# ESP-Power.net
KiCad netlist of a schematic drawn in Altium Designer
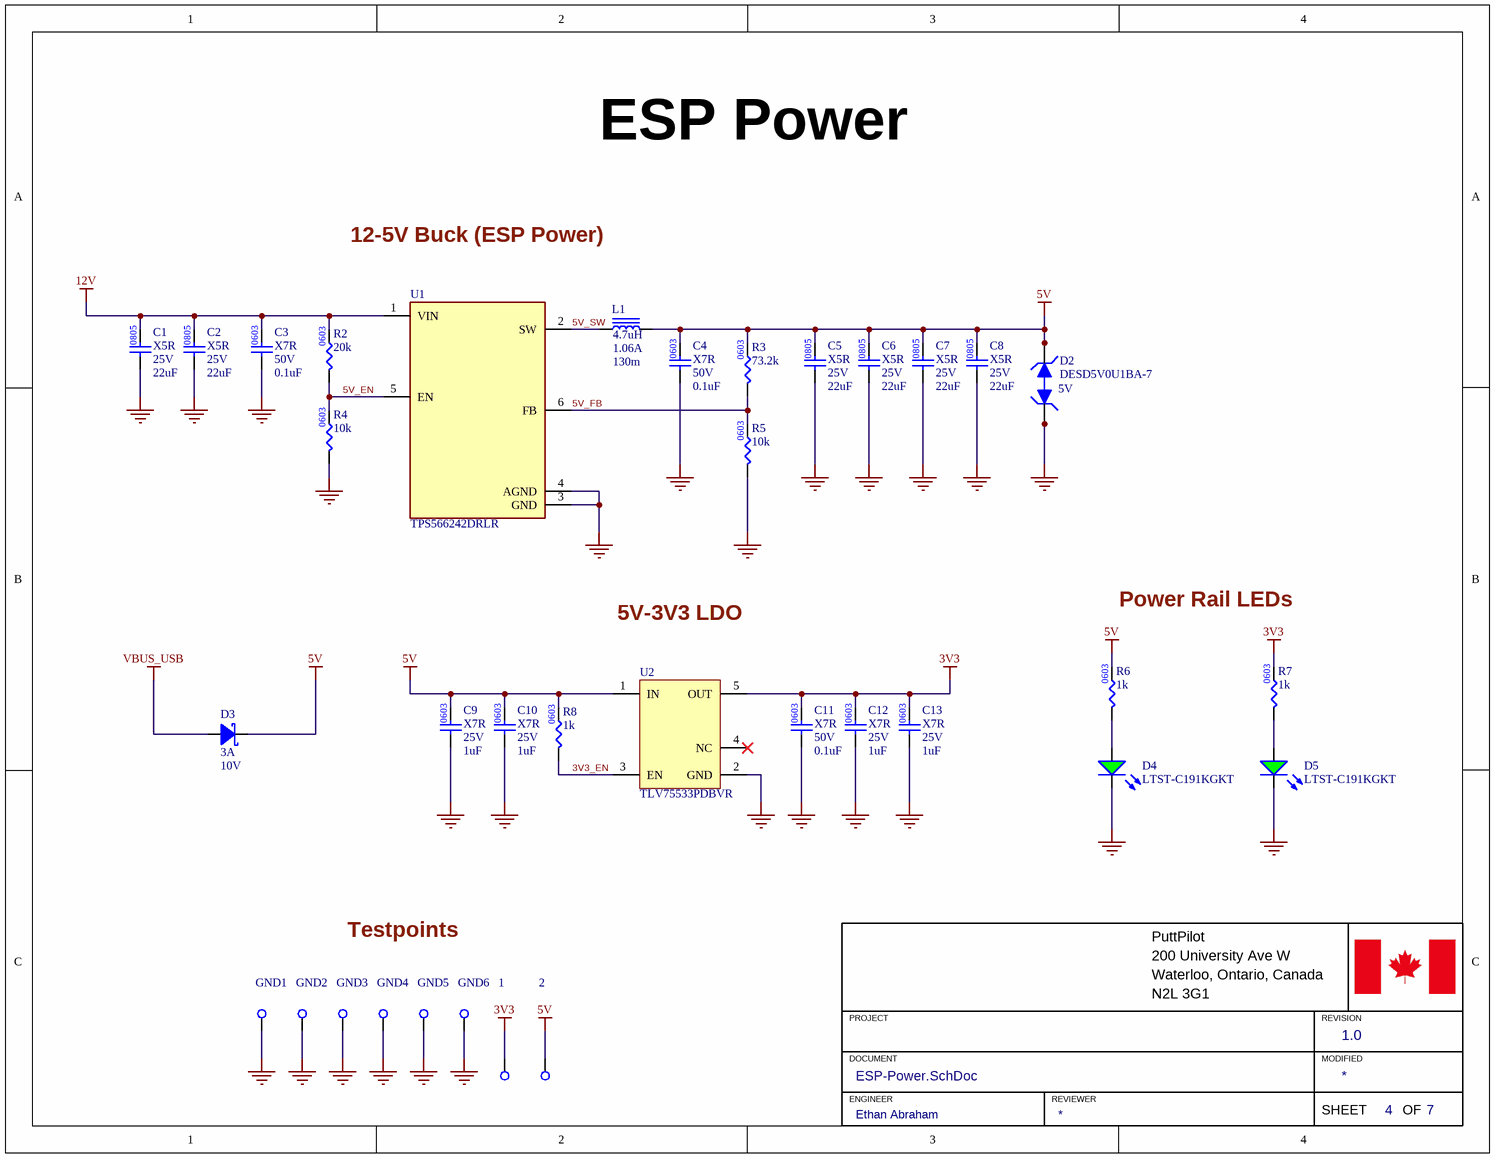
[diagram p0: ESP-Power.SchDoc]

(export (version "E")
  (design (tool "Eeschema 10.0.6"))
  (components
    (comp (ref "1")
      (value "RCWCTE")
      (footprint "RCWCTE")
      (description "SMT Test Point")
      (fields (field (name "MANUFACTURER") "KOA Speer"))
      (libsource (lib "PuttPilot") (part "RCWCTE"))
    )
    (comp (ref "2")
      (value "RCWCTE")
      (footprint "RCWCTE")
      (description "SMT Test Point")
      (fields (field (name "MANUFACTURER") "KOA Speer"))
      (libsource (lib "PuttPilot") (part "RCWCTE"))
    )
    (comp (ref "C1")
      (value "GRM21BR61E226ME44K")
      (footprint ".CAP_0805")
      (description "CAP CER 22uF 25V X5R 0805")
      (fields
        (field (name "MANUFACTURER") "Murata")
        (field (name "TEMPERATURE CHARACTERISTICS CODE") "X5R")
        (field (name "RATED DC VOLTAGE (URDC)") "25V")
        (field (name "CAPACITANCE") "22uF")
      )
      (libsource (lib "PuttPilot") (part "GRM21BR61E226ME44K"))
    )
    (comp (ref "C2")
      (value "GRM21BR61E226ME44K")
      (footprint ".CAP_0805")
      (description "CAP CER 22uF 25V X5R 0805")
      (fields
        (field (name "MANUFACTURER") "Murata")
        (field (name "TEMPERATURE CHARACTERISTICS CODE") "X5R")
        (field (name "RATED DC VOLTAGE (URDC)") "25V")
        (field (name "CAPACITANCE") "22uF")
      )
      (libsource (lib "PuttPilot") (part "GRM21BR61E226ME44K"))
    )
    (comp (ref "C3")
      (value "GCJ188R71H104KA12D")
      (footprint ".CAP_0603")
      (description "CAP CER 0.1uF 50V X7R 0603")
      (fields
        (field (name "MANUFACTURER") "Murata")
        (field (name "TEMPERATURE CHARACTERISTICS CODE") "X7R")
        (field (name "RATED DC VOLTAGE (URDC)") "50V")
        (field (name "CAPACITANCE") "0.1uF")
      )
      (libsource (lib "PuttPilot") (part "GCJ188R71H104KA12D"))
    )
    (comp (ref "C4")
      (value "GCJ188R71H104KA12D")
      (footprint ".CAP_0603")
      (description "CAP CER 0.1uF 50V X7R 0603")
      (fields
        (field (name "MANUFACTURER") "Murata")
        (field (name "TEMPERATURE CHARACTERISTICS CODE") "X7R")
        (field (name "RATED DC VOLTAGE (URDC)") "50V")
        (field (name "CAPACITANCE") "0.1uF")
      )
      (libsource (lib "PuttPilot") (part "GCJ188R71H104KA12D"))
    )
    (comp (ref "C5")
      (value "GRM21BR61E226ME44K")
      (footprint ".CAP_0805")
      (description "CAP CER 22uF 25V X5R 0805")
      (fields
        (field (name "MANUFACTURER") "Murata")
        (field (name "TEMPERATURE CHARACTERISTICS CODE") "X5R")
        (field (name "RATED DC VOLTAGE (URDC)") "25V")
        (field (name "CAPACITANCE") "22uF")
      )
      (libsource (lib "PuttPilot") (part "GRM21BR61E226ME44K"))
    )
    (comp (ref "C6")
      (value "GRM21BR61E226ME44K")
      (footprint ".CAP_0805")
      (description "CAP CER 22uF 25V X5R 0805")
      (fields
        (field (name "MANUFACTURER") "Murata")
        (field (name "TEMPERATURE CHARACTERISTICS CODE") "X5R")
        (field (name "RATED DC VOLTAGE (URDC)") "25V")
        (field (name "CAPACITANCE") "22uF")
      )
      (libsource (lib "PuttPilot") (part "GRM21BR61E226ME44K"))
    )
    (comp (ref "C7")
      (value "GRM21BR61E226ME44K")
      (footprint ".CAP_0805")
      (description "CAP CER 22uF 25V X5R 0805")
      (fields
        (field (name "MANUFACTURER") "Murata")
        (field (name "TEMPERATURE CHARACTERISTICS CODE") "X5R")
        (field (name "RATED DC VOLTAGE (URDC)") "25V")
        (field (name "CAPACITANCE") "22uF")
      )
      (libsource (lib "PuttPilot") (part "GRM21BR61E226ME44K"))
    )
    (comp (ref "C8")
      (value "GRM21BR61E226ME44K")
      (footprint ".CAP_0805")
      (description "CAP CER 22uF 25V X5R 0805")
      (fields
        (field (name "MANUFACTURER") "Murata")
        (field (name "TEMPERATURE CHARACTERISTICS CODE") "X5R")
        (field (name "RATED DC VOLTAGE (URDC)") "25V")
        (field (name "CAPACITANCE") "22uF")
      )
      (libsource (lib "PuttPilot") (part "GRM21BR61E226ME44K"))
    )
    (comp (ref "C9")
      (value "GRT188R71E105KE13D")
      (footprint ".CAP_0603")
      (description "CAP CER 1uF 25V X7R 0603")
      (fields
        (field (name "MANUFACTURER") "Murata")
        (field (name "TEMPERATURE CHARACTERISTICS CODE") "X7R")
        (field (name "RATED DC VOLTAGE (URDC)") "25V")
        (field (name "CAPACITANCE") "1uF")
      )
      (libsource (lib "PuttPilot") (part "GRT188R71E105KE13D"))
    )
    (comp (ref "C10")
      (value "GRT188R71E105KE13D")
      (footprint ".CAP_0603")
      (description "CAP CER 1uF 25V X7R 0603")
      (fields
        (field (name "MANUFACTURER") "Murata")
        (field (name "TEMPERATURE CHARACTERISTICS CODE") "X7R")
        (field (name "RATED DC VOLTAGE (URDC)") "25V")
        (field (name "CAPACITANCE") "1uF")
      )
      (libsource (lib "PuttPilot") (part "GRT188R71E105KE13D"))
    )
    (comp (ref "C11")
      (value "GCJ188R71H104KA12D")
      (footprint ".CAP_0603")
      (description "CAP CER 0.1uF 50V X7R 0603")
      (fields
        (field (name "MANUFACTURER") "Murata")
        (field (name "TEMPERATURE CHARACTERISTICS CODE") "X7R")
        (field (name "RATED DC VOLTAGE (URDC)") "50V")
        (field (name "CAPACITANCE") "0.1uF")
      )
      (libsource (lib "PuttPilot") (part "GCJ188R71H104KA12D"))
    )
    (comp (ref "C12")
      (value "GRT188R71E105KE13D")
      (footprint ".CAP_0603")
      (description "CAP CER 1uF 25V X7R 0603")
      (fields
        (field (name "MANUFACTURER") "Murata")
        (field (name "TEMPERATURE CHARACTERISTICS CODE") "X7R")
        (field (name "RATED DC VOLTAGE (URDC)") "25V")
        (field (name "CAPACITANCE") "1uF")
      )
      (libsource (lib "PuttPilot") (part "GRT188R71E105KE13D"))
    )
    (comp (ref "C13")
      (value "GRT188R71E105KE13D")
      (footprint ".CAP_0603")
      (description "CAP CER 1uF 25V X7R 0603")
      (fields
        (field (name "MANUFACTURER") "Murata")
        (field (name "TEMPERATURE CHARACTERISTICS CODE") "X7R")
        (field (name "RATED DC VOLTAGE (URDC)") "25V")
        (field (name "CAPACITANCE") "1uF")
      )
      (libsource (lib "PuttPilot") (part "GRT188R71E105KE13D"))
    )
    (comp (ref "D2")
      (value "DESD5V0U1BA-7")
      (footprint "DESD5V0U1BA-7")
      (description "TVS DIODE 5VWM")
      (fields (field (name "MANUFACTURER") "Diodes") (field (name "REP PK REVERSE VOLTAGE-MAX") "5V"))
      (libsource (lib "PuttPilot") (part "DESD5V0U1BA-7"))
    )
    (comp (ref "D3")
      (value "BAT60JFILM")
      (footprint "BAT60JFILM")
      (description "DIODE SCHOTTKY 10V 3A SOD323")
      (fields (field (name "MAX CURRENT") "3A") (field (name "MAX VOLTAGE") "10V"))
      (libsource (lib "PuttPilot") (part "BAT60JFILM"))
    )
    (comp (ref "D4")
      (value "LTST-C191KGKT")
      (footprint ".LED_0603")
      (description "LED GREEN 2V 0603")
      (fields (field (name "MANUFACTURER") "Vishay Lite-On"))
      (libsource (lib "PuttPilot") (part "LTST-C191KGKT"))
    )
    (comp (ref "D5")
      (value "LTST-C191KGKT")
      (footprint ".LED_0603")
      (description "LED GREEN 2V 0603")
      (fields (field (name "MANUFACTURER") "Vishay Lite-On"))
      (libsource (lib "PuttPilot") (part "LTST-C191KGKT"))
    )
    (comp (ref "GND1")
      (value "RCWCTE")
      (footprint "RCWCTE")
      (description "SMT Test Point")
      (fields (field (name "MANUFACTURER") "KOA Speer"))
      (libsource (lib "PuttPilot") (part "RCWCTE"))
    )
    (comp (ref "GND2")
      (value "RCWCTE")
      (footprint "RCWCTE")
      (description "SMT Test Point")
      (fields (field (name "MANUFACTURER") "KOA Speer"))
      (libsource (lib "PuttPilot") (part "RCWCTE"))
    )
    (comp (ref "GND3")
      (value "RCWCTE")
      (footprint "RCWCTE")
      (description "SMT Test Point")
      (fields (field (name "MANUFACTURER") "KOA Speer"))
      (libsource (lib "PuttPilot") (part "RCWCTE"))
    )
    (comp (ref "GND4")
      (value "RCWCTE")
      (footprint "RCWCTE")
      (description "SMT Test Point")
      (fields (field (name "MANUFACTURER") "KOA Speer"))
      (libsource (lib "PuttPilot") (part "RCWCTE"))
    )
    (comp (ref "GND5")
      (value "RCWCTE")
      (footprint "RCWCTE")
      (description "SMT Test Point")
      (fields (field (name "MANUFACTURER") "KOA Speer"))
      (libsource (lib "PuttPilot") (part "RCWCTE"))
    )
    (comp (ref "GND6")
      (value "RCWCTE")
      (footprint "RCWCTE")
      (description "SMT Test Point")
      (fields (field (name "MANUFACTURER") "KOA Speer"))
      (libsource (lib "PuttPilot") (part "RCWCTE"))
    )
    (comp (ref "L1")
      (value "NRH3012T4R7MN")
      (footprint "NRH3012T4R7MN")
      (description "FIXED IND 4.7uH 1.06A")
      (fields
        (field (name "MANUFACTURER") "Taiyo Yuden")
        (field (name "TOLERANCE") "20%")
        (field (name "DC RESISTANCE (DCR)") "130m")
        (field (name "INDUCTANCE-NOM (L)") "4.7uH")
        (field (name "RATED CURRENT-MAX") "1.06A")
      )
      (libsource (lib "PuttPilot") (part "NRH3012T4R7MN"))
    )
    (comp (ref "R2")
      (value "ERJ-3EKF2002V")
      (footprint ".RES_0603")
      (description "RES 20K OHM 0603")
      (fields
        (field (name "MANUFACTURER") "Panasonic")
        (field (name "TOLERANCE") "1%")
        (field (name "RESISTANCE") "20k")
      )
      (libsource (lib "PuttPilot") (part "ERJ-3EKF2002V"))
    )
    (comp (ref "R3")
      (value "RC0603FR-0773K2L")
      (footprint ".RES_0603")
      (description "RES 73.2K OHM 0603")
      (fields
        (field (name "MANUFACTURER") "Yageo")
        (field (name "TOLERANCE") "1%")
        (field (name "RESISTANCE") "73.2k")
      )
      (libsource (lib "PuttPilot") (part "RC0603FR-0773K2L"))
    )
    (comp (ref "R4")
      (value "RC0603FR-0710KL")
      (footprint ".RES_0603")
      (description "RES 10K OHM 0603")
      (fields
        (field (name "MANUFACTURER") "Yageo")
        (field (name "TOLERANCE") "1%")
        (field (name "RESISTANCE") "10k")
      )
      (libsource (lib "PuttPilot") (part "RC0603FR-0710KL"))
    )
    (comp (ref "R5")
      (value "RC0603FR-0710KL")
      (footprint ".RES_0603")
      (description "RES 10K OHM 0603")
      (fields
        (field (name "MANUFACTURER") "Yageo")
        (field (name "TOLERANCE") "1%")
        (field (name "RESISTANCE") "10k")
      )
      (libsource (lib "PuttPilot") (part "RC0603FR-0710KL"))
    )
    (comp (ref "R6")
      (value "RC0603FR-071KL")
      (footprint ".RES_0603")
      (description "RES 1K OHM 0603")
      (fields
        (field (name "MANUFACTURER") "Yageo")
        (field (name "TOLERANCE") "1%")
        (field (name "RESISTANCE") "1k")
      )
      (libsource (lib "PuttPilot") (part "RC0603FR-071KL"))
    )
    (comp (ref "R7")
      (value "RC0603FR-071KL")
      (footprint ".RES_0603")
      (description "RES 1K OHM 0603")
      (fields
        (field (name "MANUFACTURER") "Yageo")
        (field (name "TOLERANCE") "1%")
        (field (name "RESISTANCE") "1k")
      )
      (libsource (lib "PuttPilot") (part "RC0603FR-071KL"))
    )
    (comp (ref "R8")
      (value "RC0603FR-071KL")
      (footprint ".RES_0603")
      (description "RES 1K OHM 0603")
      (fields
        (field (name "MANUFACTURER") "Yageo")
        (field (name "TOLERANCE") "1%")
        (field (name "RESISTANCE") "1k")
      )
      (libsource (lib "PuttPilot") (part "RC0603FR-071KL"))
    )
    (comp (ref "U1")
      (value "TPS566242DRLR")
      (footprint "TPS566242DRLR")
      (description "BUCK 3V-16V 6A SOT-563")
      (fields (field (name "MANUFACTURER") "Texas Instruments"))
      (libsource (lib "PuttPilot") (part "TPS566242DRLR"))
    )
    (comp (ref "U2")
      (value "TLV75533PDBVR")
      (footprint ".SOT-23-5")
      (description "3V3 (Fixed) LDO 500mA SOT25")
      (fields (field (name "MANUFACTURER") "Texas Instruments"))
      (libsource (lib "PuttPilot") (part "TLV75533PDBVR"))
    )
  )
  (nets
    (net (code "1") (name "/3V3_EN") (class "Default")
      (node (ref "R8") (pin "1") (pinfunction "1_1") (pintype "passive"))
      (node (ref "U2") (pin "3") (pinfunction "EN_3") (pintype "passive"))
    )
    (net (code "2") (name "/5V_EN") (class "Default")
      (node (ref "R2") (pin "1") (pinfunction "1_1") (pintype "passive"))
      (node (ref "R4") (pin "2") (pinfunction "2_2") (pintype "passive"))
      (node (ref "U1") (pin "5") (pinfunction "EN_5") (pintype "passive"))
    )
    (net (code "3") (name "/5V_FB") (class "Default")
      (node (ref "R3") (pin "1") (pinfunction "1_1") (pintype "passive"))
      (node (ref "R5") (pin "2") (pinfunction "2_2") (pintype "passive"))
      (node (ref "U1") (pin "6") (pinfunction "FB_6") (pintype "passive"))
    )
    (net (code "4") (name "/5V_SW") (class "Default")
      (node (ref "L1") (pin "1") (pinfunction "1_1") (pintype "passive"))
      (node (ref "U1") (pin "2") (pinfunction "SW_2") (pintype "passive"))
    )
    (net (code "5") (name "3V3") (class "Default")
      (node (ref "1") (pin "1") (pinfunction "1_1") (pintype "passive"))
      (node (ref "C11") (pin "2") (pinfunction "2_2") (pintype "passive"))
      (node (ref "C12") (pin "2") (pinfunction "2_2") (pintype "passive"))
      (node (ref "C13") (pin "2") (pinfunction "2_2") (pintype "passive"))
      (node (ref "R7") (pin "2") (pinfunction "2_2") (pintype "passive"))
      (node (ref "U2") (pin "5") (pinfunction "OUT_5") (pintype "passive"))
    )
    (net (code "6") (name "5V") (class "Default")
      (node (ref "2") (pin "1") (pinfunction "1_1") (pintype "passive"))
      (node (ref "C10") (pin "2") (pinfunction "2_2") (pintype "passive"))
      (node (ref "C4") (pin "2") (pinfunction "2_2") (pintype "passive"))
      (node (ref "C5") (pin "2") (pinfunction "2_2") (pintype "passive"))
      (node (ref "C6") (pin "2") (pinfunction "2_2") (pintype "passive"))
      (node (ref "C7") (pin "2") (pinfunction "2_2") (pintype "passive"))
      (node (ref "C8") (pin "2") (pinfunction "2_2") (pintype "passive"))
      (node (ref "C9") (pin "2") (pinfunction "2_2") (pintype "passive"))
      (node (ref "D2") (pin "2") (pinfunction "Pin_2_2") (pintype "passive"))
      (node (ref "D3") (pin "2") (pinfunction "Cathode_2") (pintype "passive"))
      (node (ref "L1") (pin "2") (pinfunction "2_2") (pintype "passive"))
      (node (ref "R3") (pin "2") (pinfunction "2_2") (pintype "passive"))
      (node (ref "R6") (pin "2") (pinfunction "2_2") (pintype "passive"))
      (node (ref "R8") (pin "2") (pinfunction "2_2") (pintype "passive"))
      (node (ref "U2") (pin "1") (pinfunction "IN_1") (pintype "passive"))
    )
    (net (code "7") (name "12V") (class "Default")
      (node (ref "C1") (pin "2") (pinfunction "2_2") (pintype "passive"))
      (node (ref "C2") (pin "2") (pinfunction "2_2") (pintype "passive"))
      (node (ref "C3") (pin "2") (pinfunction "2_2") (pintype "passive"))
      (node (ref "R2") (pin "2") (pinfunction "2_2") (pintype "passive"))
      (node (ref "U1") (pin "1") (pinfunction "VIN_1") (pintype "passive"))
    )
    (net (code "8") (name "GND") (class "Default")
      (node (ref "C1") (pin "1") (pinfunction "1_1") (pintype "passive"))
      (node (ref "C10") (pin "1") (pinfunction "1_1") (pintype "passive"))
      (node (ref "C11") (pin "1") (pinfunction "1_1") (pintype "passive"))
      (node (ref "C12") (pin "1") (pinfunction "1_1") (pintype "passive"))
      (node (ref "C13") (pin "1") (pinfunction "1_1") (pintype "passive"))
      (node (ref "C2") (pin "1") (pinfunction "1_1") (pintype "passive"))
      (node (ref "C3") (pin "1") (pinfunction "1_1") (pintype "passive"))
      (node (ref "C4") (pin "1") (pinfunction "1_1") (pintype "passive"))
      (node (ref "C5") (pin "1") (pinfunction "1_1") (pintype "passive"))
      (node (ref "C6") (pin "1") (pinfunction "1_1") (pintype "passive"))
      (node (ref "C7") (pin "1") (pinfunction "1_1") (pintype "passive"))
      (node (ref "C8") (pin "1") (pinfunction "1_1") (pintype "passive"))
      (node (ref "C9") (pin "1") (pinfunction "1_1") (pintype "passive"))
      (node (ref "D2") (pin "1") (pinfunction "Pin_1_1") (pintype "passive"))
      (node (ref "D4") (pin "2") (pinfunction "K_2") (pintype "passive"))
      (node (ref "D5") (pin "2") (pinfunction "K_2") (pintype "passive"))
      (node (ref "GND1") (pin "1") (pinfunction "1_1") (pintype "passive"))
      (node (ref "GND2") (pin "1") (pinfunction "1_1") (pintype "passive"))
      (node (ref "GND3") (pin "1") (pinfunction "1_1") (pintype "passive"))
      (node (ref "GND4") (pin "1") (pinfunction "1_1") (pintype "passive"))
      (node (ref "GND5") (pin "1") (pinfunction "1_1") (pintype "passive"))
      (node (ref "GND6") (pin "1") (pinfunction "1_1") (pintype "passive"))
      (node (ref "R4") (pin "1") (pinfunction "1_1") (pintype "passive"))
      (node (ref "R5") (pin "1") (pinfunction "1_1") (pintype "passive"))
      (node (ref "U1") (pin "3") (pinfunction "GND_3") (pintype "passive"))
      (node (ref "U1") (pin "4") (pinfunction "AGND_4") (pintype "passive"))
      (node (ref "U2") (pin "2") (pinfunction "GND_2") (pintype "passive"))
    )
    (net (code "9") (name "Net-(D4-A)") (class "Default")
      (node (ref "D4") (pin "1") (pinfunction "A_1") (pintype "passive"))
      (node (ref "R6") (pin "1") (pinfunction "1_1") (pintype "passive"))
    )
    (net (code "10") (name "Net-(D5-A)") (class "Default")
      (node (ref "D5") (pin "1") (pinfunction "A_1") (pintype "passive"))
      (node (ref "R7") (pin "1") (pinfunction "1_1") (pintype "passive"))
    )
    (net (code "11") (name "VBUS_USB") (class "Default")
      (node (ref "D3") (pin "1") (pinfunction "Anode_1") (pintype "passive"))
    )
    (net (code "12") (name "unconnected-(U2-NC-Pad4)") (class "Default")
      (node (ref "U2") (pin "4") (pinfunction "NC_4") (pintype "passive+no_connect"))
    )
  )
)
